# power_supply_breakout_module.net
KiCad netlist of a schematic drawn in EAGLE
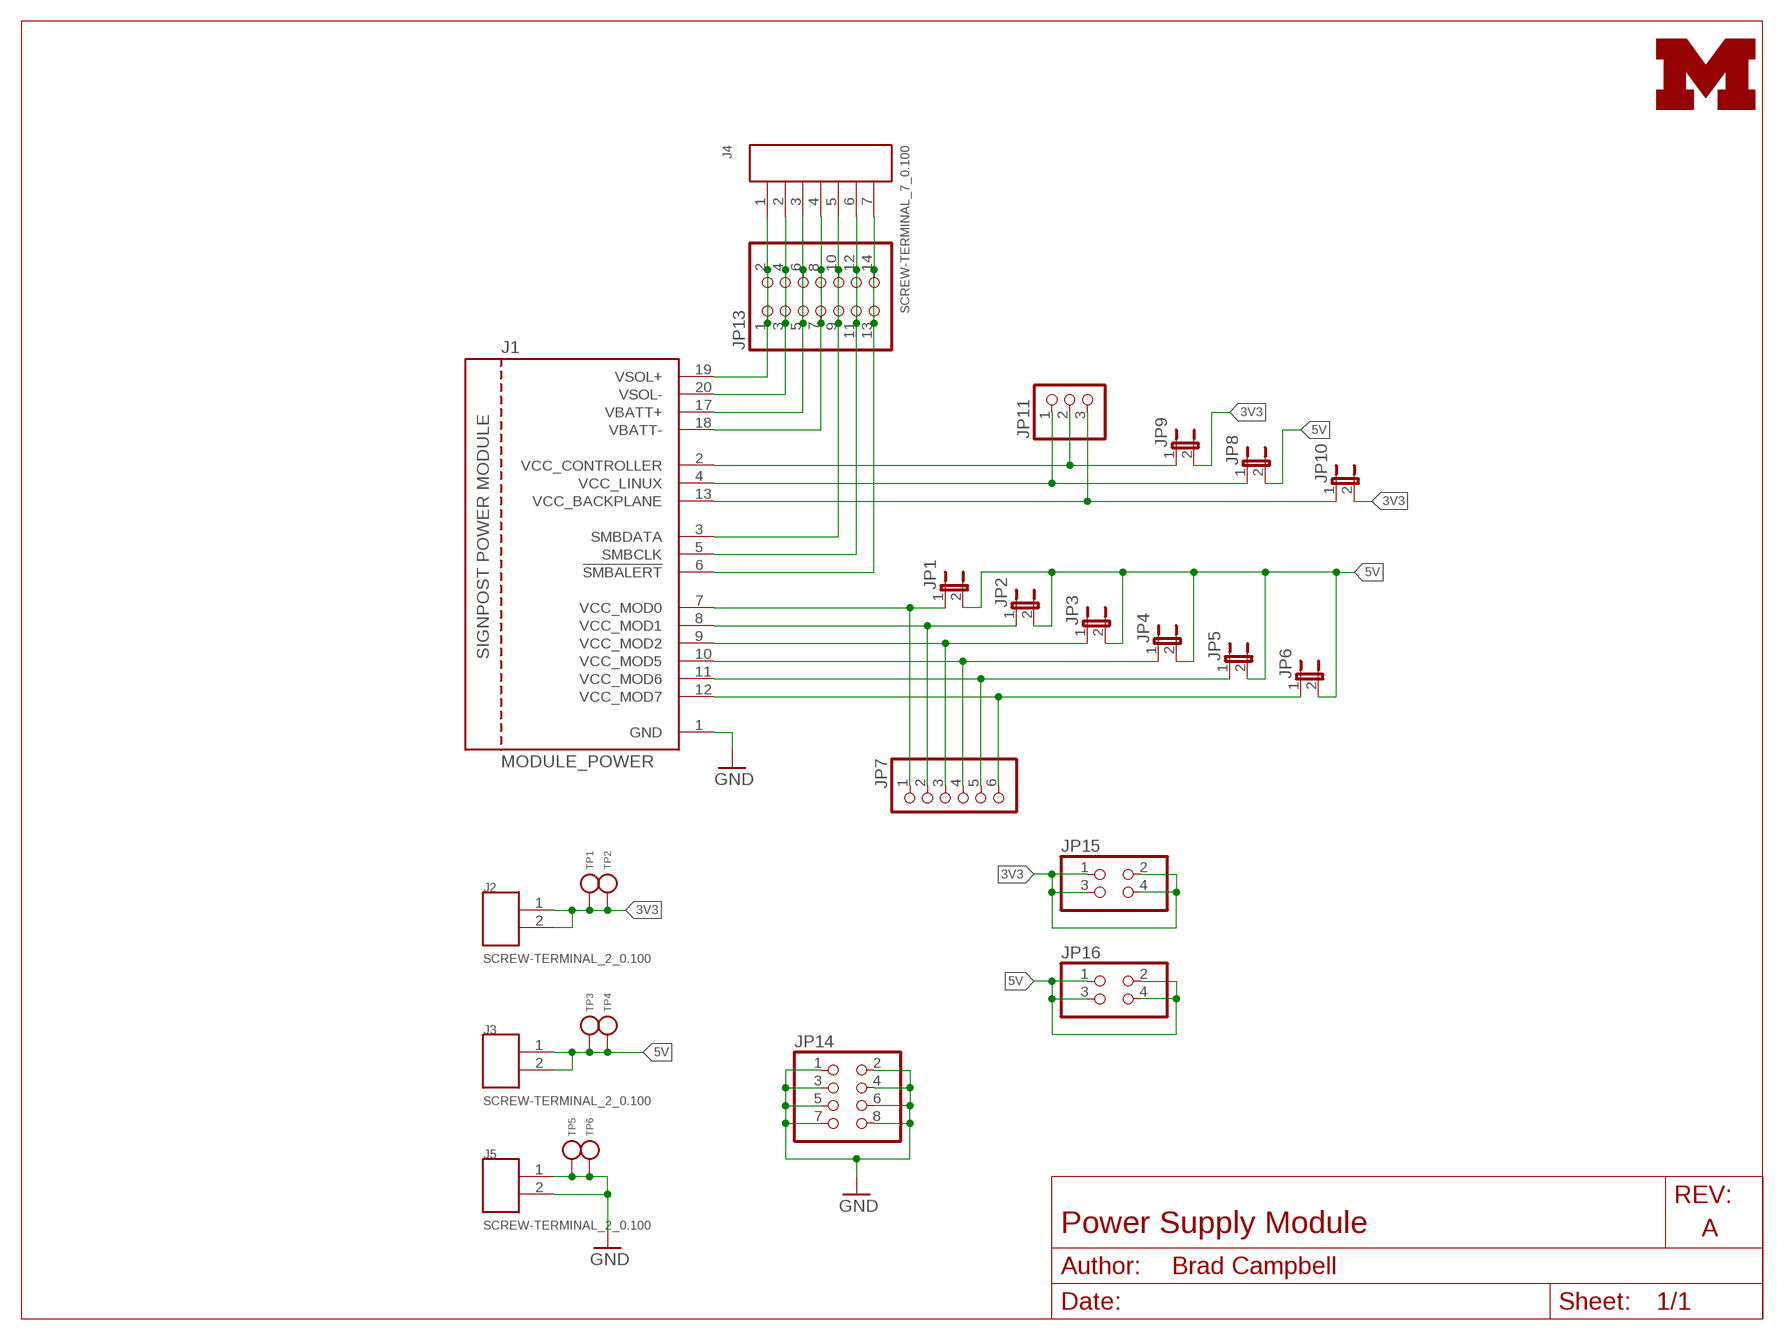
[diagram p0: schematic, sheet 1]

(export (version "E")
  (design (tool "Eeschema 10.0.6"))
  (components
    (comp (ref "J1")
      (value "MODULE_POWER")
      (footprint "eagle-import:MODULE_POWER")
      (libsource (lib "eagle-import") (part "MODULE_POWER"))
    )
    (comp (ref "J2")
      (value "SCREW-TERMINAL_2_0.100")
      (footprint "eagle-import:CONN_BLOCK_2")
      (libsource (lib "eagle-import") (part "SCREW-TERMINAL_2_0.100"))
    )
    (comp (ref "J3")
      (value "SCREW-TERMINAL_2_0.100")
      (footprint "eagle-import:CONN_BLOCK_2")
      (libsource (lib "eagle-import") (part "SCREW-TERMINAL_2_0.100"))
    )
    (comp (ref "J4")
      (value "SCREW-TERMINAL_7_0.100")
      (footprint "eagle-import:CONN_BLOCK_7")
      (libsource (lib "eagle-import") (part "SCREW-TERMINAL_7_0.100"))
    )
    (comp (ref "J5")
      (value "SCREW-TERMINAL_2_0.100")
      (footprint "eagle-import:CONN_BLOCK_2")
      (libsource (lib "eagle-import") (part "SCREW-TERMINAL_2_0.100"))
    )
    (comp (ref "JP1")
      (value "JUMPER-2PTH")
      (footprint "eagle-import:1X02")
      (libsource (lib "eagle-import") (part "JUMPER-2PTH"))
    )
    (comp (ref "JP2")
      (value "JUMPER-2PTH")
      (footprint "eagle-import:1X02")
      (libsource (lib "eagle-import") (part "JUMPER-2PTH"))
    )
    (comp (ref "JP3")
      (value "JUMPER-2PTH")
      (footprint "eagle-import:1X02")
      (libsource (lib "eagle-import") (part "JUMPER-2PTH"))
    )
    (comp (ref "JP4")
      (value "JUMPER-2PTH")
      (footprint "eagle-import:1X02")
      (libsource (lib "eagle-import") (part "JUMPER-2PTH"))
    )
    (comp (ref "JP5")
      (value "JUMPER-2PTH")
      (footprint "eagle-import:1X02")
      (libsource (lib "eagle-import") (part "JUMPER-2PTH"))
    )
    (comp (ref "JP6")
      (value "JUMPER-2PTH")
      (footprint "eagle-import:1X02")
      (libsource (lib "eagle-import") (part "JUMPER-2PTH"))
    )
    (comp (ref "JP7")
      (value "PINHD-1X6")
      (footprint "eagle-import:1X06")
      (libsource (lib "eagle-import") (part "PINHD-1X6"))
    )
    (comp (ref "JP8")
      (value "JUMPER-2PTH")
      (footprint "eagle-import:1X02")
      (libsource (lib "eagle-import") (part "JUMPER-2PTH"))
    )
    (comp (ref "JP9")
      (value "JUMPER-2PTH")
      (footprint "eagle-import:1X02")
      (libsource (lib "eagle-import") (part "JUMPER-2PTH"))
    )
    (comp (ref "JP10")
      (value "JUMPER-2PTH")
      (footprint "eagle-import:1X02")
      (libsource (lib "eagle-import") (part "JUMPER-2PTH"))
    )
    (comp (ref "JP11")
      (value "PINHD-1X3")
      (footprint "eagle-import:1X03")
      (libsource (lib "eagle-import") (part "PINHD-1X3"))
    )
    (comp (ref "JP13")
      (value "PINHD-2X7")
      (footprint "eagle-import:2X07")
      (libsource (lib "eagle-import") (part "PINHD-2X7"))
    )
    (comp (ref "JP14")
      (value "PINHD-2X4")
      (footprint "eagle-import:2X04")
      (libsource (lib "eagle-import") (part "PINHD-2X4"))
    )
    (comp (ref "JP15")
      (value "PINHD-2X2")
      (footprint "eagle-import:2X02")
      (libsource (lib "eagle-import") (part "PINHD-2X2"))
    )
    (comp (ref "JP16")
      (value "PINHD-2X2")
      (footprint "eagle-import:2X02")
      (libsource (lib "eagle-import") (part "PINHD-2X2"))
    )
    (comp (ref "LOGO1")
      (value "UMICH_SOLID_MEDIUM")
      (footprint "eagle-import:UMICH_SOLID_200MIL")
      (libsource (lib "eagle-import") (part "UMICH_SOLID_MEDIUM"))
    )
    (comp (ref "TP1")
      (value "TEST_POINT_0.040IN")
      (footprint "eagle-import:TESTPOINT_0.040IN")
      (libsource (lib "eagle-import") (part "TEST_POINT_0.040IN"))
    )
    (comp (ref "TP2")
      (value "TEST_POINT_0.040IN")
      (footprint "eagle-import:TESTPOINT_0.040IN")
      (libsource (lib "eagle-import") (part "TEST_POINT_0.040IN"))
    )
    (comp (ref "TP3")
      (value "TEST_POINT_0.040IN")
      (footprint "eagle-import:TESTPOINT_0.040IN")
      (libsource (lib "eagle-import") (part "TEST_POINT_0.040IN"))
    )
    (comp (ref "TP4")
      (value "TEST_POINT_0.040IN")
      (footprint "eagle-import:TESTPOINT_0.040IN")
      (libsource (lib "eagle-import") (part "TEST_POINT_0.040IN"))
    )
    (comp (ref "TP5")
      (value "TEST_POINT_0.040IN")
      (footprint "eagle-import:TESTPOINT_0.040IN")
      (libsource (lib "eagle-import") (part "TEST_POINT_0.040IN"))
    )
    (comp (ref "TP6")
      (value "TEST_POINT_0.040IN")
      (footprint "eagle-import:TESTPOINT_0.040IN")
      (libsource (lib "eagle-import") (part "TEST_POINT_0.040IN"))
    )
  )
  (nets
    (net (code "1") (name "3V3") (class "Default")
      (node (ref "J2") (pin "1") (pinfunction "1_1") (pintype "bidirectional"))
      (node (ref "J2") (pin "2") (pinfunction "2_2") (pintype "bidirectional"))
      (node (ref "JP10") (pin "2") (pinfunction "2_2") (pintype "passive"))
      (node (ref "JP15") (pin "1") (pinfunction "1_1") (pintype "passive"))
      (node (ref "JP15") (pin "2") (pinfunction "2_2") (pintype "passive"))
      (node (ref "JP15") (pin "3") (pinfunction "3_3") (pintype "passive"))
      (node (ref "JP15") (pin "4") (pinfunction "4_4") (pintype "passive"))
      (node (ref "JP9") (pin "2") (pinfunction "2_2") (pintype "passive"))
      (node (ref "TP1") (pin "TESTPOINT") (pinfunction "TESTPOINT_TESTPOINT") (pintype "bidirectional"))
      (node (ref "TP2") (pin "TESTPOINT") (pinfunction "TESTPOINT_TESTPOINT") (pintype "bidirectional"))
    )
    (net (code "2") (name "5V") (class "Default")
      (node (ref "J3") (pin "1") (pinfunction "1_1") (pintype "bidirectional"))
      (node (ref "J3") (pin "2") (pinfunction "2_2") (pintype "bidirectional"))
      (node (ref "JP1") (pin "2") (pinfunction "2_2") (pintype "passive"))
      (node (ref "JP16") (pin "1") (pinfunction "1_1") (pintype "passive"))
      (node (ref "JP16") (pin "2") (pinfunction "2_2") (pintype "passive"))
      (node (ref "JP16") (pin "3") (pinfunction "3_3") (pintype "passive"))
      (node (ref "JP16") (pin "4") (pinfunction "4_4") (pintype "passive"))
      (node (ref "JP2") (pin "2") (pinfunction "2_2") (pintype "passive"))
      (node (ref "JP3") (pin "2") (pinfunction "2_2") (pintype "passive"))
      (node (ref "JP4") (pin "2") (pinfunction "2_2") (pintype "passive"))
      (node (ref "JP5") (pin "2") (pinfunction "2_2") (pintype "passive"))
      (node (ref "JP6") (pin "2") (pinfunction "2_2") (pintype "passive"))
      (node (ref "JP8") (pin "2") (pinfunction "2_2") (pintype "passive"))
      (node (ref "TP3") (pin "TESTPOINT") (pinfunction "TESTPOINT_TESTPOINT") (pintype "bidirectional"))
      (node (ref "TP4") (pin "TESTPOINT") (pinfunction "TESTPOINT_TESTPOINT") (pintype "bidirectional"))
    )
    (net (code "3") (name "GND") (class "Default")
      (node (ref "J1") (pin "1") (pinfunction "GND_1") (pintype "power_in"))
      (node (ref "J5") (pin "1") (pinfunction "1_1") (pintype "bidirectional"))
      (node (ref "J5") (pin "2") (pinfunction "2_2") (pintype "bidirectional"))
      (node (ref "JP14") (pin "1") (pinfunction "1_1") (pintype "passive"))
      (node (ref "JP14") (pin "2") (pinfunction "2_2") (pintype "passive"))
      (node (ref "JP14") (pin "3") (pinfunction "3_3") (pintype "passive"))
      (node (ref "JP14") (pin "4") (pinfunction "4_4") (pintype "passive"))
      (node (ref "JP14") (pin "5") (pinfunction "5_5") (pintype "passive"))
      (node (ref "JP14") (pin "6") (pinfunction "6_6") (pintype "passive"))
      (node (ref "JP14") (pin "7") (pinfunction "7_7") (pintype "passive"))
      (node (ref "JP14") (pin "8") (pinfunction "8_8") (pintype "passive"))
      (node (ref "TP5") (pin "TESTPOINT") (pinfunction "TESTPOINT_TESTPOINT") (pintype "bidirectional"))
      (node (ref "TP6") (pin "TESTPOINT") (pinfunction "TESTPOINT_TESTPOINT") (pintype "bidirectional"))
    )
    (net (code "4") (name "Net-(J1-SMBCLK)") (class "Default")
      (node (ref "J1") (pin "5") (pinfunction "SMBCLK_5") (pintype "open_collector"))
      (node (ref "J4") (pin "6") (pinfunction "6_6") (pintype "bidirectional"))
      (node (ref "JP13") (pin "11") (pinfunction "11_11") (pintype "passive"))
      (node (ref "JP13") (pin "12") (pinfunction "12_12") (pintype "passive"))
    )
    (net (code "5") (name "Net-(J1-SMBDATA)") (class "Default")
      (node (ref "J1") (pin "3") (pinfunction "SMBDATA_3") (pintype "open_collector"))
      (node (ref "J4") (pin "5") (pinfunction "5_5") (pintype "bidirectional"))
      (node (ref "JP13") (pin "10") (pinfunction "10_10") (pintype "passive"))
      (node (ref "JP13") (pin "9") (pinfunction "9_9") (pintype "passive"))
    )
    (net (code "6") (name "Net-(J1-VBATT+)") (class "Default")
      (node (ref "J1") (pin "17") (pinfunction "VBATT+_17") (pintype "power_in"))
      (node (ref "J4") (pin "3") (pinfunction "3_3") (pintype "bidirectional"))
      (node (ref "JP13") (pin "5") (pinfunction "5_5") (pintype "passive"))
      (node (ref "JP13") (pin "6") (pinfunction "6_6") (pintype "passive"))
    )
    (net (code "7") (name "Net-(J1-VBATT-)") (class "Default")
      (node (ref "J1") (pin "18") (pinfunction "VBATT-_18") (pintype "power_in"))
      (node (ref "J4") (pin "4") (pinfunction "4_4") (pintype "bidirectional"))
      (node (ref "JP13") (pin "7") (pinfunction "7_7") (pintype "passive"))
      (node (ref "JP13") (pin "8") (pinfunction "8_8") (pintype "passive"))
    )
    (net (code "8") (name "Net-(J1-VCC_BACKPLANE)") (class "Default")
      (node (ref "J1") (pin "13") (pinfunction "VCC_BACKPLANE_13") (pintype "power_in"))
      (node (ref "JP10") (pin "1") (pinfunction "1_1") (pintype "passive"))
      (node (ref "JP11") (pin "3") (pinfunction "3_3") (pintype "passive"))
    )
    (net (code "9") (name "Net-(J1-VCC_CONTROLLER)") (class "Default")
      (node (ref "J1") (pin "2") (pinfunction "VCC_CONTROLLER_2") (pintype "power_in"))
      (node (ref "JP11") (pin "2") (pinfunction "2_2") (pintype "passive"))
      (node (ref "JP9") (pin "1") (pinfunction "1_1") (pintype "passive"))
    )
    (net (code "10") (name "Net-(J1-VCC_LINUX)") (class "Default")
      (node (ref "J1") (pin "4") (pinfunction "VCC_LINUX_4") (pintype "power_in"))
      (node (ref "JP11") (pin "1") (pinfunction "1_1") (pintype "passive"))
      (node (ref "JP8") (pin "1") (pinfunction "1_1") (pintype "passive"))
    )
    (net (code "11") (name "Net-(J1-VCC_MOD0)") (class "Default")
      (node (ref "J1") (pin "7") (pinfunction "VCC_MOD0_7") (pintype "power_in"))
      (node (ref "JP1") (pin "1") (pinfunction "1_1") (pintype "passive"))
      (node (ref "JP7") (pin "1") (pinfunction "1_1") (pintype "passive"))
    )
    (net (code "12") (name "Net-(J1-VCC_MOD1)") (class "Default")
      (node (ref "J1") (pin "8") (pinfunction "VCC_MOD1_8") (pintype "power_in"))
      (node (ref "JP2") (pin "1") (pinfunction "1_1") (pintype "passive"))
      (node (ref "JP7") (pin "2") (pinfunction "2_2") (pintype "passive"))
    )
    (net (code "13") (name "Net-(J1-VCC_MOD2)") (class "Default")
      (node (ref "J1") (pin "9") (pinfunction "VCC_MOD2_9") (pintype "power_in"))
      (node (ref "JP3") (pin "1") (pinfunction "1_1") (pintype "passive"))
      (node (ref "JP7") (pin "3") (pinfunction "3_3") (pintype "passive"))
    )
    (net (code "14") (name "Net-(J1-VCC_MOD5)") (class "Default")
      (node (ref "J1") (pin "10") (pinfunction "VCC_MOD5_10") (pintype "power_in"))
      (node (ref "JP4") (pin "1") (pinfunction "1_1") (pintype "passive"))
      (node (ref "JP7") (pin "4") (pinfunction "4_4") (pintype "passive"))
    )
    (net (code "15") (name "Net-(J1-VCC_MOD6)") (class "Default")
      (node (ref "J1") (pin "11") (pinfunction "VCC_MOD6_11") (pintype "power_in"))
      (node (ref "JP5") (pin "1") (pinfunction "1_1") (pintype "passive"))
      (node (ref "JP7") (pin "5") (pinfunction "5_5") (pintype "passive"))
    )
    (net (code "16") (name "Net-(J1-VCC_MOD7)") (class "Default")
      (node (ref "J1") (pin "12") (pinfunction "VCC_MOD7_12") (pintype "power_in"))
      (node (ref "JP6") (pin "1") (pinfunction "1_1") (pintype "passive"))
      (node (ref "JP7") (pin "6") (pinfunction "6_6") (pintype "passive"))
    )
    (net (code "17") (name "Net-(J1-VSOL+)") (class "Default")
      (node (ref "J1") (pin "19") (pinfunction "VSOL+_19") (pintype "power_in"))
      (node (ref "J4") (pin "1") (pinfunction "1_1") (pintype "bidirectional"))
      (node (ref "JP13") (pin "1") (pinfunction "1_1") (pintype "passive"))
      (node (ref "JP13") (pin "2") (pinfunction "2_2") (pintype "passive"))
    )
    (net (code "18") (name "Net-(J1-VSOL-)") (class "Default")
      (node (ref "J1") (pin "20") (pinfunction "VSOL-_20") (pintype "power_in"))
      (node (ref "J4") (pin "2") (pinfunction "2_2") (pintype "bidirectional"))
      (node (ref "JP13") (pin "3") (pinfunction "3_3") (pintype "passive"))
      (node (ref "JP13") (pin "4") (pinfunction "4_4") (pintype "passive"))
    )
    (net (code "19") (name "Net-(J1-~{SMBALERT})") (class "Default")
      (node (ref "J1") (pin "6") (pinfunction "~{SMBALERT}_6") (pintype "bidirectional"))
      (node (ref "J4") (pin "7") (pinfunction "7_7") (pintype "bidirectional"))
      (node (ref "JP13") (pin "13") (pinfunction "13_13") (pintype "passive"))
      (node (ref "JP13") (pin "14") (pinfunction "14_14") (pintype "passive"))
    )
  )
)
